# STM32.net
KiCad netlist of a schematic drawn in Altium Designer
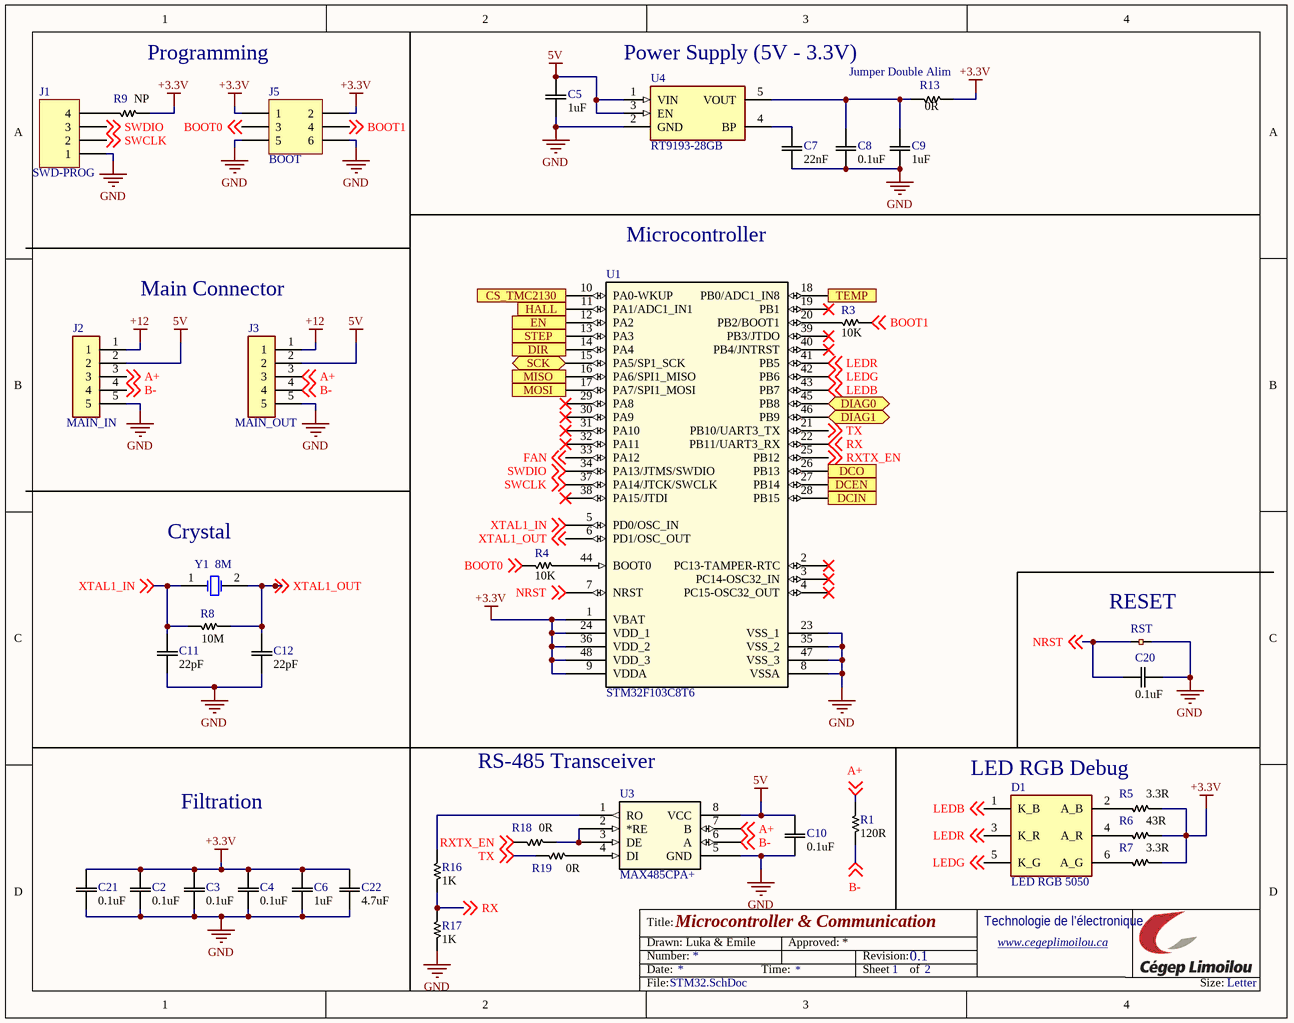
[diagram p0: STM32.SchDoc]

(export (version "E")
  (design (tool "Eeschema 10.0.6"))
  (components
    (comp (ref "C2")
      (value "0.1uF")
      (footprint "0603")
      (description "Capacitor SMD 0603")
      (fields
        (field (name "MANUFACTURER_PART_NUMBER") "12065A820JAT2A")
        (field (name "Comment") "Capacitor SMD")
        (field (name "COPYRIGHT") "Copyright (C) 2018 Accelerated Designs. All rights reserved")
      )
      (libsource (lib "Schematic_Emile") (part "Capacitor SMD"))
    )
    (comp (ref "C3")
      (value "0.1uF")
      (footprint "0603")
      (description "Capacitor SMD 0603")
      (fields
        (field (name "MANUFACTURER_PART_NUMBER") "12065A820JAT2A")
        (field (name "Comment") "Capacitor SMD")
        (field (name "COPYRIGHT") "Copyright (C) 2018 Accelerated Designs. All rights reserved")
      )
      (libsource (lib "Schematic_Emile") (part "Capacitor SMD"))
    )
    (comp (ref "C4")
      (value "0.1uF")
      (footprint "0603")
      (description "Capacitor SMD 0603")
      (fields
        (field (name "MANUFACTURER_PART_NUMBER") "12065A820JAT2A")
        (field (name "Comment") "Capacitor SMD")
        (field (name "COPYRIGHT") "Copyright (C) 2018 Accelerated Designs. All rights reserved")
      )
      (libsource (lib "Schematic_Emile") (part "Capacitor SMD"))
    )
    (comp (ref "C5")
      (value "1uF")
      (footprint "0603")
      (description "Capacitor SMD 0603")
      (fields
        (field (name "MANUFACTURER_PART_NUMBER") "12065A820JAT2A")
        (field (name "Comment") "Capacitor SMD")
        (field (name "COPYRIGHT") "Copyright (C) 2018 Accelerated Designs. All rights reserved")
      )
      (libsource (lib "Schematic_Emile") (part "Capacitor SMD"))
    )
    (comp (ref "C6")
      (value "1uF")
      (footprint "0603")
      (description "Capacitor SMD 0603")
      (fields
        (field (name "MANUFACTURER_PART_NUMBER") "12065A820JAT2A")
        (field (name "Comment") "Capacitor SMD")
        (field (name "COPYRIGHT") "Copyright (C) 2018 Accelerated Designs. All rights reserved")
      )
      (libsource (lib "Schematic_Emile") (part "Capacitor SMD"))
    )
    (comp (ref "C7")
      (value "22nF")
      (footprint "0603")
      (description "Capacitor SMD 0603")
      (fields
        (field (name "MANUFACTURER_PART_NUMBER") "12065A820JAT2A")
        (field (name "Comment") "Capacitor SMD")
        (field (name "COPYRIGHT") "Copyright (C) 2018 Accelerated Designs. All rights reserved")
      )
      (libsource (lib "Schematic_Emile") (part "Capacitor SMD"))
    )
    (comp (ref "C8")
      (value "0.1uF")
      (footprint "0603")
      (description "Capacitor SMD 0603")
      (fields
        (field (name "MANUFACTURER_PART_NUMBER") "12065A820JAT2A")
        (field (name "Comment") "Capacitor SMD")
        (field (name "COPYRIGHT") "Copyright (C) 2018 Accelerated Designs. All rights reserved")
      )
      (libsource (lib "Schematic_Emile") (part "Capacitor SMD"))
    )
    (comp (ref "C9")
      (value "1uF")
      (footprint "0603")
      (description "Capacitor SMD 0603")
      (fields
        (field (name "MANUFACTURER_PART_NUMBER") "12065A820JAT2A")
        (field (name "Comment") "Capacitor SMD")
        (field (name "COPYRIGHT") "Copyright (C) 2018 Accelerated Designs. All rights reserved")
      )
      (libsource (lib "Schematic_Emile") (part "Capacitor SMD"))
    )
    (comp (ref "C10")
      (value "0.1uF")
      (footprint "0603")
      (description "Capacitor SMD 0603")
      (fields
        (field (name "MANUFACTURER_PART_NUMBER") "12065A820JAT2A")
        (field (name "Comment") "Capacitor SMD")
        (field (name "COPYRIGHT") "Copyright (C) 2018 Accelerated Designs. All rights reserved")
      )
      (libsource (lib "Schematic_Emile") (part "Capacitor SMD"))
    )
    (comp (ref "C11")
      (value "22pF")
      (footprint "0603")
      (description "Capacitor SMD 0603")
      (fields
        (field (name "MANUFACTURER_PART_NUMBER") "12065A820JAT2A")
        (field (name "Comment") "Capacitor SMD")
        (field (name "COPYRIGHT") "Copyright (C) 2018 Accelerated Designs. All rights reserved")
      )
      (libsource (lib "Schematic_Emile") (part "Capacitor SMD"))
    )
    (comp (ref "C12")
      (value "22pF")
      (footprint "0603")
      (description "Capacitor SMD 0603")
      (fields
        (field (name "MANUFACTURER_PART_NUMBER") "12065A820JAT2A")
        (field (name "Comment") "Capacitor SMD")
        (field (name "COPYRIGHT") "Copyright (C) 2018 Accelerated Designs. All rights reserved")
      )
      (libsource (lib "Schematic_Emile") (part "Capacitor SMD"))
    )
    (comp (ref "C20")
      (value "0.1uF")
      (footprint "0603")
      (description "Capacitor SMD 0603")
      (fields
        (field (name "MANUFACTURER_PART_NUMBER") "12065A820JAT2A")
        (field (name "Comment") "Capacitor SMD")
        (field (name "COPYRIGHT") "Copyright (C) 2018 Accelerated Designs. All rights reserved")
      )
      (libsource (lib "Schematic_Emile") (part "Capacitor SMD"))
    )
    (comp (ref "C21")
      (value "0.1uF")
      (footprint "0603")
      (description "Capacitor SMD 0603")
      (fields
        (field (name "MANUFACTURER_PART_NUMBER") "12065A820JAT2A")
        (field (name "Comment") "Capacitor SMD")
        (field (name "COPYRIGHT") "Copyright (C) 2018 Accelerated Designs. All rights reserved")
      )
      (libsource (lib "Schematic_Emile") (part "Capacitor SMD"))
    )
    (comp (ref "C22")
      (value "4.7uF")
      (footprint "0603")
      (description "Capacitor SMD 0603")
      (fields
        (field (name "MANUFACTURER_PART_NUMBER") "12065A820JAT2A")
        (field (name "Comment") "Capacitor SMD")
        (field (name "COPYRIGHT") "Copyright (C) 2018 Accelerated Designs. All rights reserved")
      )
      (libsource (lib "Schematic_Emile") (part "Capacitor SMD"))
    )
    (comp (ref "D1")
      (value "LED RGB 5050")
      (footprint "LED 5050")
      (description "LED")
      (fields
        (field (name "MANUFACTURER_PART_NUMBER") "150505M173300")
        (field (name "MOUSER PART NUMBER") "710-150505M173300")
      )
      (libsource (lib "Schematic_Emile") (part "150505M173300"))
    )
    (comp (ref "J1")
      (value "SWD-PROG")
      (footprint "HDR1X4")
      (description "Header, 4-Pin")
      (fields (field (name "PUBLISHER") "Altium Limited"))
      (libsource (lib "Miscellaneous Connectors") (part "Header 4"))
    )
    (comp (ref "J2")
      (value "MAIN_IN")
      (footprint "JST 5POS 2.5mm 90°")
      (description "Connector")
      (fields (field (name "MANUFACTURER_PART_NUMBER") "S5B-XH-A-1(LF)(SN)"))
      (libsource (lib "Schematic_Emile") (part "JST 5POS"))
    )
    (comp (ref "J3")
      (value "MAIN_OUT")
      (footprint "JST 5POS 2.5mm 90°")
      (description "Connector")
      (fields (field (name "MANUFACTURER_PART_NUMBER") "S5B-XH-A-1(LF)(SN)"))
      (libsource (lib "Schematic_Emile") (part "JST 5POS"))
    )
    (comp (ref "J5")
      (value "BOOT")
      (footprint "Header 3x2 1.27mm SMD")
      (description "Header, 3-Pin, Dual row")
      (fields (field (name "PUBLISHER") "Altium Limited"))
      (libsource (lib "Miscellaneous Connectors") (part "Header 3X2"))
    )
    (comp (ref "R1")
      (value "120R")
      (footprint "0603")
      (description "Resistor 0603 SMD")
      (fields
        (field (name "MANUFACTURER_PART_NUMBER") "ERJ8CWFR024V")
        (field (name "Comment") "Resistor 0603")
        (field (name "COPYRIGHT") "Copyright (C) 2018 Accelerated Designs. All rights reserved")
      )
      (libsource (lib "Schematic_Emile") (part "Resistor 0603"))
    )
    (comp (ref "R3")
      (value "10K")
      (footprint "0603")
      (description "Resistor 0603 SMD")
      (fields
        (field (name "MANUFACTURER_PART_NUMBER") "ERJ8CWFR024V")
        (field (name "Comment") "Resistor 0603")
        (field (name "COPYRIGHT") "Copyright (C) 2018 Accelerated Designs. All rights reserved")
      )
      (libsource (lib "Schematic_Emile") (part "Resistor 0603"))
    )
    (comp (ref "R4")
      (value "10K")
      (footprint "0603")
      (description "Resistor 0603 SMD")
      (fields
        (field (name "MANUFACTURER_PART_NUMBER") "ERJ8CWFR024V")
        (field (name "Comment") "Resistor 0603")
        (field (name "COPYRIGHT") "Copyright (C) 2018 Accelerated Designs. All rights reserved")
      )
      (libsource (lib "Schematic_Emile") (part "Resistor 0603"))
    )
    (comp (ref "R5")
      (value "3.3R")
      (footprint "0603")
      (description "Resistor 0603 SMD")
      (fields
        (field (name "MANUFACTURER_PART_NUMBER") "ERJ8CWFR024V")
        (field (name "Comment") "Resistor 0603")
        (field (name "COPYRIGHT") "Copyright (C) 2018 Accelerated Designs. All rights reserved")
      )
      (libsource (lib "Schematic_Emile") (part "Resistor 0603"))
    )
    (comp (ref "R6")
      (value "43R")
      (footprint "0603")
      (description "Resistor 0603 SMD")
      (fields
        (field (name "MANUFACTURER_PART_NUMBER") "ERJ8CWFR024V")
        (field (name "Comment") "Resistor 0603")
        (field (name "COPYRIGHT") "Copyright (C) 2018 Accelerated Designs. All rights reserved")
      )
      (libsource (lib "Schematic_Emile") (part "Resistor 0603"))
    )
    (comp (ref "R7")
      (value "3.3R")
      (footprint "0603")
      (description "Resistor 0603 SMD")
      (fields
        (field (name "MANUFACTURER_PART_NUMBER") "ERJ8CWFR024V")
        (field (name "Comment") "Resistor 0603")
        (field (name "COPYRIGHT") "Copyright (C) 2018 Accelerated Designs. All rights reserved")
      )
      (libsource (lib "Schematic_Emile") (part "Resistor 0603"))
    )
    (comp (ref "R8")
      (value "10M")
      (footprint "0603")
      (description "Resistor 0603 SMD")
      (fields
        (field (name "MANUFACTURER_PART_NUMBER") "ERJ8CWFR024V")
        (field (name "Comment") "Resistor 0603")
        (field (name "COPYRIGHT") "Copyright (C) 2018 Accelerated Designs. All rights reserved")
      )
      (libsource (lib "Schematic_Emile") (part "Resistor 0603"))
    )
    (comp (ref "R9")
      (value "NP")
      (footprint "0603")
      (description "Resistor 0603 SMD")
      (fields
        (field (name "MANUFACTURER_PART_NUMBER") "ERJ8CWFR024V")
        (field (name "Comment") "Resistor 0603")
        (field (name "COPYRIGHT") "Copyright (C) 2018 Accelerated Designs. All rights reserved")
      )
      (libsource (lib "Schematic_Emile") (part "Resistor 0603"))
    )
    (comp (ref "R13")
      (value "0R")
      (footprint "0603")
      (description "Resistor 0603 SMD")
      (fields
        (field (name "MANUFACTURER_PART_NUMBER") "ERJ8CWFR024V")
        (field (name "Comment") "Resistor 0603")
        (field (name "COPYRIGHT") "Copyright (C) 2018 Accelerated Designs. All rights reserved")
      )
      (libsource (lib "Schematic_Emile") (part "Resistor 0603"))
    )
    (comp (ref "R16")
      (value "1K")
      (footprint "0603")
      (description "Resistor 0603 SMD")
      (fields
        (field (name "MANUFACTURER_PART_NUMBER") "ERJ8CWFR024V")
        (field (name "Comment") "Resistor 0603")
        (field (name "COPYRIGHT") "Copyright (C) 2018 Accelerated Designs. All rights reserved")
      )
      (libsource (lib "Schematic_Emile") (part "Resistor 0603"))
    )
    (comp (ref "R17")
      (value "1K")
      (footprint "0603")
      (description "Resistor 0603 SMD")
      (fields
        (field (name "MANUFACTURER_PART_NUMBER") "ERJ8CWFR024V")
        (field (name "Comment") "Resistor 0603")
        (field (name "COPYRIGHT") "Copyright (C) 2018 Accelerated Designs. All rights reserved")
      )
      (libsource (lib "Schematic_Emile") (part "Resistor 0603"))
    )
    (comp (ref "R18")
      (value "0R")
      (footprint "0603")
      (description "Resistor 0603 SMD")
      (fields
        (field (name "MANUFACTURER_PART_NUMBER") "ERJ8CWFR024V")
        (field (name "Comment") "Resistor 0603")
        (field (name "COPYRIGHT") "Copyright (C) 2018 Accelerated Designs. All rights reserved")
      )
      (libsource (lib "Schematic_Emile") (part "Resistor 0603"))
    )
    (comp (ref "R19")
      (value "0R")
      (footprint "0603")
      (description "Resistor 0603 SMD")
      (fields
        (field (name "MANUFACTURER_PART_NUMBER") "ERJ8CWFR024V")
        (field (name "Comment") "Resistor 0603")
        (field (name "COPYRIGHT") "Copyright (C) 2018 Accelerated Designs. All rights reserved")
      )
      (libsource (lib "Schematic_Emile") (part "Resistor 0603"))
    )
    (comp (ref "RST")
      (value "PAD RST")
      (footprint "PAD")
      (description "SMD Pad for contact")
      (libsource (lib "Schematic_Emile") (part "PAD"))
    )
    (comp (ref "U1")
      (value "STM32F103C8T6")
      (footprint "LQFP-48")
      (description "Integrated Circuit STM32")
      (fields (field (name "COPYRIGHT") "Copyright (C) 2018 Accelerated Designs. All rights reserved"))
      (libsource (lib "Schematic_Emile") (part "STM32F103C8T6"))
    )
    (comp (ref "U3")
      (value "MAX485CPA+")
      (footprint "DIP 8 - 3D")
      (description "RS485 Communication")
      (fields (field (name "COPYRIGHT") "Copyright (C) 2018 Accelerated Designs. All rights reserved"))
      (libsource (lib "Schematic_Emile") (part "MAX485CPA+"))
    )
    (comp (ref "U4")
      (value "RT9193-28GB")
      (footprint "SamacSys:SOT94P279X130-5N")
      (description "Voltage Regulator 3.3V")
      (libsource (lib "Schematic_Emile") (part "RT9193-28GB"))
    )
    (comp (ref "Y1")
      (value "8M")
      (footprint "ATS080B-E")
      (description "Crystal Oscillator")
      (fields (field (name "PUBLISHER") "Altium Limited"))
      (libsource (lib "Miscellaneous Devices") (part "XTAL"))
    )
  )
  (nets
    (net (code "1") (name "+3.3V") (class "Default")
      (node (ref "C2") (pin "2") (pinfunction "2_2") (pintype "passive"))
      (node (ref "C21") (pin "2") (pinfunction "2_2") (pintype "passive"))
      (node (ref "C22") (pin "2") (pinfunction "2_2") (pintype "passive"))
      (node (ref "C3") (pin "2") (pinfunction "2_2") (pintype "passive"))
      (node (ref "C4") (pin "2") (pinfunction "2_2") (pintype "passive"))
      (node (ref "C6") (pin "2") (pinfunction "2_2") (pintype "passive"))
      (node (ref "J5") (pin "1") (pinfunction "1_1") (pintype "passive"))
      (node (ref "J5") (pin "2") (pinfunction "2_2") (pintype "passive"))
      (node (ref "R13") (pin "2") (pinfunction "2_2") (pintype "passive"))
      (node (ref "R5") (pin "2") (pinfunction "2_2") (pintype "passive"))
      (node (ref "R6") (pin "2") (pinfunction "2_2") (pintype "passive"))
      (node (ref "R7") (pin "2") (pinfunction "2_2") (pintype "passive"))
      (node (ref "R9") (pin "2") (pinfunction "2_2") (pintype "passive"))
      (node (ref "U1") (pin "1") (pinfunction "VBAT_1") (pintype "power_in"))
      (node (ref "U1") (pin "24") (pinfunction "VDD_1_24") (pintype "power_in"))
      (node (ref "U1") (pin "36") (pinfunction "VDD_2_36") (pintype "power_in"))
      (node (ref "U1") (pin "48") (pinfunction "VDD_3_48") (pintype "power_in"))
      (node (ref "U1") (pin "9") (pinfunction "VDDA_9") (pintype "power_in"))
    )
    (net (code "2") (name "+12") (class "Default")
      (node (ref "J2") (pin "1") (pinfunction "1_1") (pintype "passive"))
      (node (ref "J3") (pin "1") (pinfunction "1_1") (pintype "passive"))
    )
    (net (code "3") (name "/CS_TMC2130") (class "Default")
      (node (ref "U1") (pin "10") (pinfunction "PA0-WKUP_10") (pintype "bidirectional"))
    )
    (net (code "4") (name "/DCEN") (class "Default")
      (node (ref "U1") (pin "27") (pinfunction "PB14_27") (pintype "bidirectional"))
    )
    (net (code "5") (name "/DCIN") (class "Default")
      (node (ref "U1") (pin "28") (pinfunction "PB15_28") (pintype "bidirectional"))
    )
    (net (code "6") (name "/DCO") (class "Default")
      (node (ref "U1") (pin "26") (pinfunction "PB13_26") (pintype "bidirectional"))
    )
    (net (code "7") (name "/DIAG0") (class "Default")
      (node (ref "U1") (pin "45") (pinfunction "PB8_45") (pintype "bidirectional"))
    )
    (net (code "8") (name "/DIAG1") (class "Default")
      (node (ref "U1") (pin "46") (pinfunction "PB9_46") (pintype "bidirectional"))
    )
    (net (code "9") (name "/DIR") (class "Default")
      (node (ref "U1") (pin "14") (pinfunction "PA4_14") (pintype "bidirectional"))
    )
    (net (code "10") (name "/EN") (class "Default")
      (node (ref "U1") (pin "12") (pinfunction "PA2_12") (pintype "bidirectional"))
    )
    (net (code "11") (name "/HALL") (class "Default")
      (node (ref "U1") (pin "11") (pinfunction "PA1/ADC1_IN1_11") (pintype "bidirectional"))
    )
    (net (code "12") (name "/MISO") (class "Default")
      (node (ref "U1") (pin "16") (pinfunction "PA6/SPI1_MISO_16") (pintype "bidirectional"))
    )
    (net (code "13") (name "/MOSI") (class "Default")
      (node (ref "U1") (pin "17") (pinfunction "PA7/SPI1_MOSI_17") (pintype "bidirectional"))
    )
    (net (code "14") (name "/SCK") (class "Default")
      (node (ref "U1") (pin "15") (pinfunction "PA5/SP1_SCK_15") (pintype "bidirectional"))
    )
    (net (code "15") (name "/STEP") (class "Default")
      (node (ref "U1") (pin "13") (pinfunction "PA3_13") (pintype "bidirectional"))
    )
    (net (code "16") (name "/TEMP") (class "Default")
      (node (ref "U1") (pin "18") (pinfunction "PB0/ADC1_IN8_18") (pintype "bidirectional"))
    )
    (net (code "17") (name "5V") (class "Default")
      (node (ref "C10") (pin "2") (pinfunction "2_2") (pintype "passive"))
      (node (ref "C5") (pin "2") (pinfunction "2_2") (pintype "passive"))
      (node (ref "J2") (pin "2") (pinfunction "2_2") (pintype "passive"))
      (node (ref "J3") (pin "2") (pinfunction "2_2") (pintype "passive"))
      (node (ref "U3") (pin "8") (pinfunction "VCC_8") (pintype "power_in"))
      (node (ref "U4") (pin "1") (pinfunction "VIN_1") (pintype "input"))
      (node (ref "U4") (pin "3") (pinfunction "EN_3") (pintype "input"))
    )
    (net (code "18") (name "A+") (class "Default")
      (node (ref "J2") (pin "3") (pinfunction "3_3") (pintype "passive"))
      (node (ref "J3") (pin "3") (pinfunction "3_3") (pintype "passive"))
      (node (ref "R1") (pin "2") (pinfunction "2_2") (pintype "passive"))
      (node (ref "U3") (pin "7") (pinfunction "B_7") (pintype "bidirectional"))
    )
    (net (code "19") (name "B-") (class "Default")
      (node (ref "J2") (pin "4") (pinfunction "4_4") (pintype "passive"))
      (node (ref "J3") (pin "4") (pinfunction "4_4") (pintype "passive"))
      (node (ref "R1") (pin "1") (pinfunction "1_1") (pintype "passive"))
      (node (ref "U3") (pin "6") (pinfunction "A_6") (pintype "bidirectional"))
    )
    (net (code "20") (name "BOOT0") (class "Default")
      (node (ref "J5") (pin "3") (pinfunction "3_3") (pintype "passive"))
      (node (ref "R4") (pin "1") (pinfunction "1_1") (pintype "passive"))
    )
    (net (code "21") (name "BOOT1") (class "Default")
      (node (ref "J5") (pin "4") (pinfunction "4_4") (pintype "passive"))
      (node (ref "R3") (pin "2") (pinfunction "2_2") (pintype "passive"))
    )
    (net (code "22") (name "FAN") (class "Default")
      (node (ref "U1") (pin "33") (pinfunction "PA12_33") (pintype "bidirectional"))
    )
    (net (code "23") (name "GND") (class "Default")
      (node (ref "C10") (pin "1") (pinfunction "1_1") (pintype "passive"))
      (node (ref "C11") (pin "1") (pinfunction "1_1") (pintype "passive"))
      (node (ref "C12") (pin "1") (pinfunction "1_1") (pintype "passive"))
      (node (ref "C2") (pin "1") (pinfunction "1_1") (pintype "passive"))
      (node (ref "C20") (pin "1") (pinfunction "1_1") (pintype "passive"))
      (node (ref "C21") (pin "1") (pinfunction "1_1") (pintype "passive"))
      (node (ref "C22") (pin "1") (pinfunction "1_1") (pintype "passive"))
      (node (ref "C3") (pin "1") (pinfunction "1_1") (pintype "passive"))
      (node (ref "C4") (pin "1") (pinfunction "1_1") (pintype "passive"))
      (node (ref "C5") (pin "1") (pinfunction "1_1") (pintype "passive"))
      (node (ref "C6") (pin "1") (pinfunction "1_1") (pintype "passive"))
      (node (ref "C7") (pin "1") (pinfunction "1_1") (pintype "passive"))
      (node (ref "C8") (pin "1") (pinfunction "1_1") (pintype "passive"))
      (node (ref "C9") (pin "1") (pinfunction "1_1") (pintype "passive"))
      (node (ref "J1") (pin "1") (pinfunction "1_1") (pintype "passive"))
      (node (ref "J2") (pin "5") (pinfunction "5_5") (pintype "passive"))
      (node (ref "J3") (pin "5") (pinfunction "5_5") (pintype "passive"))
      (node (ref "J5") (pin "5") (pinfunction "5_5") (pintype "passive"))
      (node (ref "J5") (pin "6") (pinfunction "6_6") (pintype "passive"))
      (node (ref "R17") (pin "2") (pinfunction "2_2") (pintype "passive"))
      (node (ref "RST") (pin "1") (pinfunction "1_1") (pintype "passive"))
      (node (ref "U1") (pin "23") (pinfunction "VSS_1_23") (pintype "power_in"))
      (node (ref "U1") (pin "35") (pinfunction "VSS_2_35") (pintype "power_in"))
      (node (ref "U1") (pin "47") (pinfunction "VSS_3_47") (pintype "power_in"))
      (node (ref "U1") (pin "8") (pinfunction "VSSA_8") (pintype "power_in"))
      (node (ref "U3") (pin "5") (pinfunction "GND_5") (pintype "power_in"))
      (node (ref "U4") (pin "2") (pinfunction "GND_2") (pintype "power_in"))
    )
    (net (code "24") (name "LEDB") (class "Default")
      (node (ref "D1") (pin "1") (pinfunction "K_B_1") (pintype "passive"))
      (node (ref "U1") (pin "43") (pinfunction "PB7_43") (pintype "bidirectional"))
    )
    (net (code "25") (name "LEDG") (class "Default")
      (node (ref "D1") (pin "5") (pinfunction "K_G_5") (pintype "passive"))
      (node (ref "U1") (pin "42") (pinfunction "PB6_42") (pintype "bidirectional"))
    )
    (net (code "26") (name "LEDR") (class "Default")
      (node (ref "D1") (pin "3") (pinfunction "K_R_3") (pintype "passive"))
      (node (ref "U1") (pin "41") (pinfunction "PB5_41") (pintype "bidirectional"))
    )
    (net (code "27") (name "NRST") (class "Default")
      (node (ref "C20") (pin "2") (pinfunction "2_2") (pintype "passive"))
      (node (ref "RST") (pin "2") (pinfunction "2_2") (pintype "passive"))
      (node (ref "U1") (pin "7") (pinfunction "NRST_7") (pintype "bidirectional"))
    )
    (net (code "28") (name "Net-(D1-A_B)") (class "Default")
      (node (ref "D1") (pin "2") (pinfunction "A_B_2") (pintype "passive"))
      (node (ref "R5") (pin "1") (pinfunction "1_1") (pintype "passive"))
    )
    (net (code "29") (name "Net-(D1-A_G)") (class "Default")
      (node (ref "D1") (pin "6") (pinfunction "A_G_6") (pintype "passive"))
      (node (ref "R7") (pin "1") (pinfunction "1_1") (pintype "passive"))
    )
    (net (code "30") (name "Net-(D1-A_R)") (class "Default")
      (node (ref "D1") (pin "4") (pinfunction "A_R_4") (pintype "passive"))
      (node (ref "R6") (pin "1") (pinfunction "1_1") (pintype "passive"))
    )
    (net (code "31") (name "Net-(J1-Pad4)") (class "Default")
      (node (ref "J1") (pin "4") (pinfunction "4_4") (pintype "passive"))
      (node (ref "R9") (pin "1") (pinfunction "1_1") (pintype "passive"))
    )
    (net (code "32") (name "Net-(U1-BOOT0)") (class "Default")
      (node (ref "R4") (pin "2") (pinfunction "2_2") (pintype "passive"))
      (node (ref "U1") (pin "44") (pinfunction "BOOT0_44") (pintype "input"))
    )
    (net (code "33") (name "Net-(U1-PB2{slash}BOOT1)") (class "Default")
      (node (ref "R3") (pin "1") (pinfunction "1_1") (pintype "passive"))
      (node (ref "U1") (pin "20") (pinfunction "PB2/BOOT1_20") (pintype "bidirectional"))
    )
    (net (code "34") (name "Net-(U3-*RE)") (class "Default")
      (node (ref "R18") (pin "2") (pinfunction "2_2") (pintype "passive"))
      (node (ref "U3") (pin "2") (pinfunction "*RE_2") (pintype "input"))
      (node (ref "U3") (pin "3") (pinfunction "DE_3") (pintype "input"))
    )
    (net (code "35") (name "Net-(U3-DI)") (class "Default")
      (node (ref "R19") (pin "2") (pinfunction "2_2") (pintype "passive"))
      (node (ref "U3") (pin "4") (pinfunction "DI_4") (pintype "input"))
    )
    (net (code "36") (name "Net-(U3-RO)") (class "Default")
      (node (ref "R16") (pin "1") (pinfunction "1_1") (pintype "passive"))
      (node (ref "U3") (pin "1") (pinfunction "RO_1") (pintype "output"))
    )
    (net (code "37") (name "Net-(U4-BP)") (class "Default")
      (node (ref "C7") (pin "2") (pinfunction "2_2") (pintype "passive"))
      (node (ref "U4") (pin "4") (pinfunction "BP_4") (pintype "passive"))
    )
    (net (code "38") (name "Net-(U4-VOUT)") (class "Default")
      (node (ref "C8") (pin "2") (pinfunction "2_2") (pintype "passive"))
      (node (ref "C9") (pin "2") (pinfunction "2_2") (pintype "passive"))
      (node (ref "R13") (pin "1") (pinfunction "1_1") (pintype "passive"))
      (node (ref "U4") (pin "5") (pinfunction "VOUT_5") (pintype "passive"))
    )
    (net (code "39") (name "RX") (class "Default")
      (node (ref "R16") (pin "2") (pinfunction "2_2") (pintype "passive"))
      (node (ref "R17") (pin "1") (pinfunction "1_1") (pintype "passive"))
      (node (ref "U1") (pin "22") (pinfunction "PB11/UART3_RX_22") (pintype "bidirectional"))
    )
    (net (code "40") (name "RXTX_EN") (class "Default")
      (node (ref "R18") (pin "1") (pinfunction "1_1") (pintype "passive"))
      (node (ref "U1") (pin "25") (pinfunction "PB12_25") (pintype "bidirectional"))
    )
    (net (code "41") (name "SWCLK") (class "Default")
      (node (ref "J1") (pin "2") (pinfunction "2_2") (pintype "passive"))
      (node (ref "U1") (pin "37") (pinfunction "PA14/JTCK/SWCLK_37") (pintype "bidirectional"))
    )
    (net (code "42") (name "SWDIO") (class "Default")
      (node (ref "J1") (pin "3") (pinfunction "3_3") (pintype "passive"))
      (node (ref "U1") (pin "34") (pinfunction "PA13/JTMS/SWDIO_34") (pintype "bidirectional"))
    )
    (net (code "43") (name "TX") (class "Default")
      (node (ref "R19") (pin "1") (pinfunction "1_1") (pintype "passive"))
      (node (ref "U1") (pin "21") (pinfunction "PB10/UART3_TX_21") (pintype "bidirectional"))
    )
    (net (code "44") (name "XTAL1_IN") (class "Default")
      (node (ref "C11") (pin "2") (pinfunction "2_2") (pintype "passive"))
      (node (ref "R8") (pin "1") (pinfunction "1_1") (pintype "passive"))
      (node (ref "U1") (pin "5") (pinfunction "PD0/OSC_IN_5") (pintype "bidirectional"))
      (node (ref "Y1") (pin "1") (pinfunction "OSC1_1") (pintype "passive"))
    )
    (net (code "45") (name "XTAL1_OUT") (class "Default")
      (node (ref "C12") (pin "2") (pinfunction "2_2") (pintype "passive"))
      (node (ref "R8") (pin "2") (pinfunction "2_2") (pintype "passive"))
      (node (ref "U1") (pin "6") (pinfunction "PD1/OSC_OUT_6") (pintype "bidirectional"))
      (node (ref "Y1") (pin "2") (pinfunction "OSC2_2") (pintype "passive"))
    )
    (net (code "46") (name "unconnected-(U1-PA8-Pad29)") (class "Default")
      (node (ref "U1") (pin "29") (pinfunction "PA8_29") (pintype "bidirectional+no_connect"))
    )
    (net (code "47") (name "unconnected-(U1-PA9-Pad30)") (class "Default")
      (node (ref "U1") (pin "30") (pinfunction "PA9_30") (pintype "bidirectional+no_connect"))
    )
    (net (code "48") (name "unconnected-(U1-PA10-Pad31)") (class "Default")
      (node (ref "U1") (pin "31") (pinfunction "PA10_31") (pintype "bidirectional+no_connect"))
    )
    (net (code "49") (name "unconnected-(U1-PA11-Pad32)") (class "Default")
      (node (ref "U1") (pin "32") (pinfunction "PA11_32") (pintype "bidirectional+no_connect"))
    )
    (net (code "50") (name "unconnected-(U1-PA15{slash}JTDI-Pad38)") (class "Default")
      (node (ref "U1") (pin "38") (pinfunction "PA15/JTDI_38") (pintype "bidirectional+no_connect"))
    )
    (net (code "51") (name "unconnected-(U1-PB1-Pad19)") (class "Default")
      (node (ref "U1") (pin "19") (pinfunction "PB1_19") (pintype "bidirectional+no_connect"))
    )
    (net (code "52") (name "unconnected-(U1-PB3{slash}JTDO-Pad39)") (class "Default")
      (node (ref "U1") (pin "39") (pinfunction "PB3/JTDO_39") (pintype "bidirectional+no_connect"))
    )
    (net (code "53") (name "unconnected-(U1-PB4{slash}JNTRST-Pad40)") (class "Default")
      (node (ref "U1") (pin "40") (pinfunction "PB4/JNTRST_40") (pintype "bidirectional+no_connect"))
    )
    (net (code "54") (name "unconnected-(U1-PC13-TAMPER-RTC-Pad2)") (class "Default")
      (node (ref "U1") (pin "2") (pinfunction "PC13-TAMPER-RTC_2") (pintype "bidirectional+no_connect"))
    )
    (net (code "55") (name "unconnected-(U1-PC14-OSC32_IN-Pad3)") (class "Default")
      (node (ref "U1") (pin "3") (pinfunction "PC14-OSC32_IN_3") (pintype "bidirectional+no_connect"))
    )
    (net (code "56") (name "unconnected-(U1-PC15-OSC32_OUT-Pad4)") (class "Default")
      (node (ref "U1") (pin "4") (pinfunction "PC15-OSC32_OUT_4") (pintype "bidirectional+no_connect"))
    )
  )
)
